# mapleSDuino-V0_1_011-eagle7.net
KiCad netlist of a schematic drawn in EAGLE
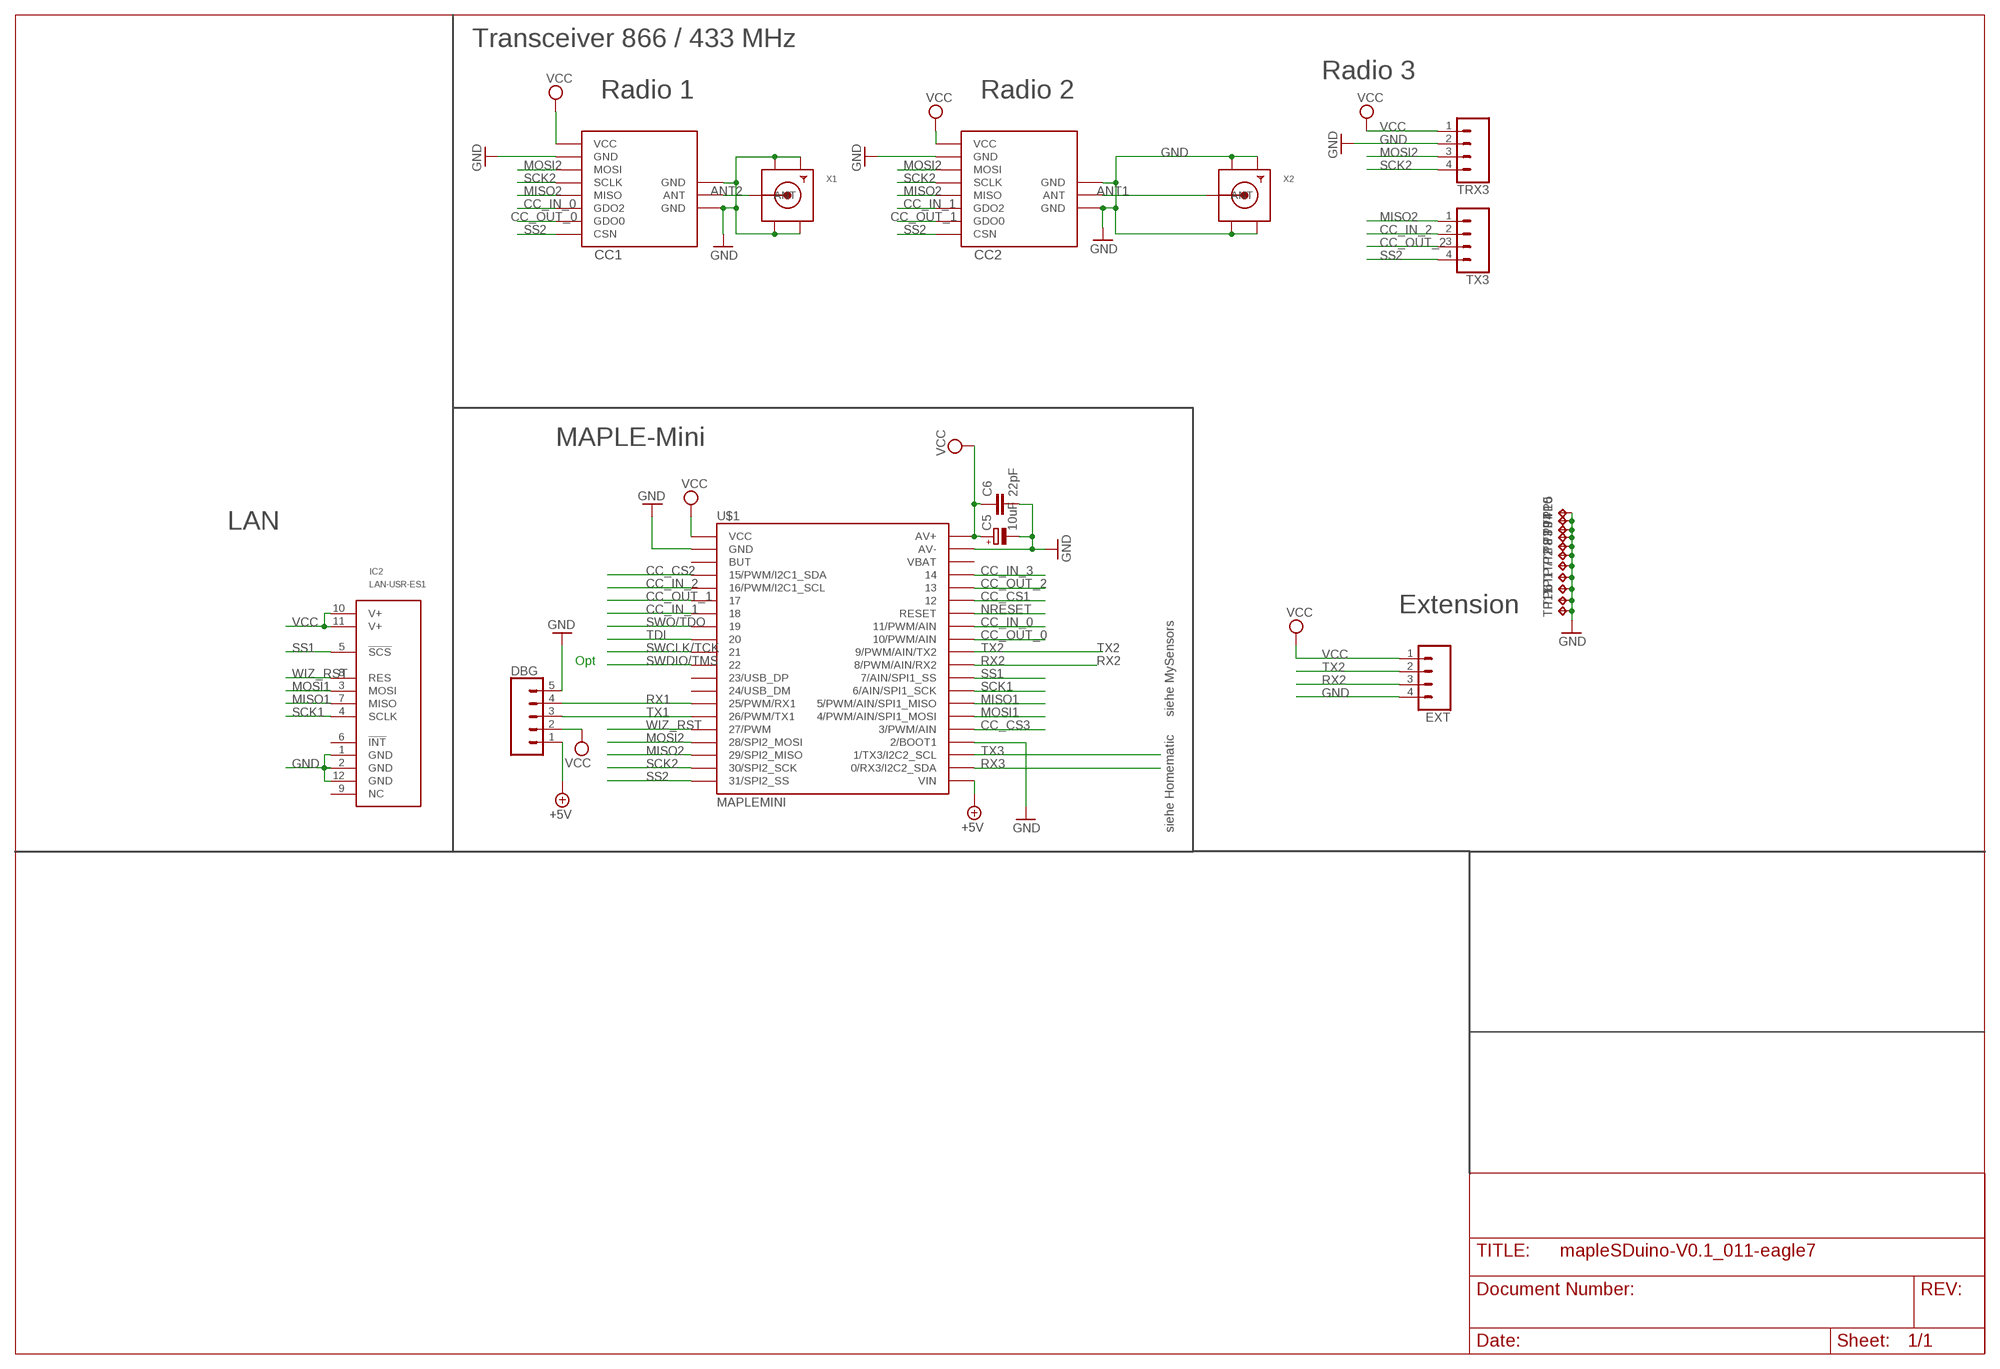
[diagram p0: schematic, sheet 1]

(export (version "E")
  (design (tool "Eeschema 10.0.6"))
  (components
    (comp (ref "C5")
      (value "10uF")
      (footprint "eagle-import:R_2012-12W")
      (libsource (lib "eagle-import") (part "CPOL-EUR/2012-12W"))
    )
    (comp (ref "C6")
      (value "22pF")
      (footprint "eagle-import:C0805")
      (libsource (lib "eagle-import") (part "C-EUC0805"))
    )
    (comp (ref "CC1")
      (value "CC1101")
      (footprint "eagle-import:CC1101_MODULE1_SMD")
      (libsource (lib "eagle-import") (part "CC1101_MODULE1SMD"))
    )
    (comp (ref "CC2")
      (value "CC1101_MODULE1SMD")
      (footprint "eagle-import:CC1101_MODULE1_SMD")
      (libsource (lib "eagle-import") (part "CC1101_MODULE1SMD"))
    )
    (comp (ref "DBG")
      (value "CONN_05LOCK")
      (footprint "eagle-import:1X05_LOCK")
      (libsource (lib "eagle-import") (part "CONN_05LOCK"))
    )
    (comp (ref "EXT")
      (value "CONN_04PTH")
      (footprint "eagle-import:1X04")
      (libsource (lib "eagle-import") (part "CONN_04PTH"))
    )
    (comp (ref "IC2")
      (value "LAN-USR-ES1")
      (footprint "eagle-import:USR-ES1")
      (libsource (lib "eagle-import") (part "LAN-USR-ES1"))
    )
    (comp (ref "TP1")
      (value "TPTP06SQ")
      (footprint "eagle-import:TP06SQ")
      (libsource (lib "eagle-import") (part "TPTP06SQ"))
    )
    (comp (ref "TP2")
      (value "TPTP06SQ")
      (footprint "eagle-import:TP06SQ")
      (libsource (lib "eagle-import") (part "TPTP06SQ"))
    )
    (comp (ref "TP3")
      (value "TPTP06SQ")
      (footprint "eagle-import:TP06SQ")
      (libsource (lib "eagle-import") (part "TPTP06SQ"))
    )
    (comp (ref "TP4")
      (value "TPTP06SQ")
      (footprint "eagle-import:TP06SQ")
      (libsource (lib "eagle-import") (part "TPTP06SQ"))
    )
    (comp (ref "TP5")
      (value "TPTP06SQ")
      (footprint "eagle-import:TP06SQ")
      (libsource (lib "eagle-import") (part "TPTP06SQ"))
    )
    (comp (ref "TP6")
      (value "TPTP06SQ")
      (footprint "eagle-import:TP06SQ")
      (libsource (lib "eagle-import") (part "TPTP06SQ"))
    )
    (comp (ref "TP7")
      (value "TPTP06SQ")
      (footprint "eagle-import:TP06SQ")
      (libsource (lib "eagle-import") (part "TPTP06SQ"))
    )
    (comp (ref "TP8")
      (value "TPTP06SQ")
      (footprint "eagle-import:TP06SQ")
      (libsource (lib "eagle-import") (part "TPTP06SQ"))
    )
    (comp (ref "TP9")
      (value "TPTP06SQ")
      (footprint "eagle-import:TP06SQ")
      (libsource (lib "eagle-import") (part "TPTP06SQ"))
    )
    (comp (ref "TP10")
      (value "TPTP06SQ")
      (footprint "eagle-import:TP06SQ")
      (libsource (lib "eagle-import") (part "TPTP06SQ"))
    )
    (comp (ref "TP11")
      (value "TPTP06SQ")
      (footprint "eagle-import:TP06SQ")
      (libsource (lib "eagle-import") (part "TPTP06SQ"))
    )
    (comp (ref "TRX3")
      (value "CONN_04PTH")
      (footprint "eagle-import:1X04")
      (libsource (lib "eagle-import") (part "CONN_04PTH"))
    )
    (comp (ref "TX3")
      (value "CONN_04PTH")
      (footprint "eagle-import:1X04")
      (libsource (lib "eagle-import") (part "CONN_04PTH"))
    )
    (comp (ref "U$1")
      (value "MAPLEMINI")
      (footprint "eagle-import:20-DIP")
      (libsource (lib "eagle-import") (part "MAPLEMINI"))
    )
    (comp (ref "X1")
      (value "SMACONNECTOR_EDGE")
      (footprint "eagle-import:SMA_EDGELAUNCH")
      (libsource (lib "eagle-import") (part "SMACONNECTOR_EDGE"))
    )
    (comp (ref "X2")
      (value "SMACONNECTOR_EDGE")
      (footprint "eagle-import:SMA_EDGELAUNCH")
      (libsource (lib "eagle-import") (part "SMACONNECTOR_EDGE"))
    )
  )
  (nets
    (net (code "1") (name "+5V") (class "Default")
      (node (ref "DBG") (pin "1") (pinfunction "1_1") (pintype "passive"))
      (node (ref "U$1") (pin "21") (pinfunction "VIN_21") (pintype "bidirectional"))
    )
    (net (code "2") (name "/ANT1") (class "Default")
      (node (ref "CC2") (pin "ANT") (pinfunction "ANT_ANT") (pintype "output"))
      (node (ref "X2") (pin "P") (pinfunction "ANT_P") (pintype "bidirectional"))
    )
    (net (code "3") (name "/ANT2") (class "Default")
      (node (ref "CC1") (pin "ANT") (pinfunction "ANT_ANT") (pintype "output"))
      (node (ref "X1") (pin "P") (pinfunction "ANT_P") (pintype "bidirectional"))
    )
    (net (code "4") (name "/CC_CS1") (class "Default")
      (node (ref "U$1") (pin "35") (pinfunction "12_35") (pintype "bidirectional"))
    )
    (net (code "5") (name "/CC_CS2") (class "Default")
      (node (ref "U$1") (pin "4") (pinfunction "15/PWM/I2C1_SDA_4") (pintype "bidirectional"))
    )
    (net (code "6") (name "/CC_CS3") (class "Default")
      (node (ref "U$1") (pin "25") (pinfunction "3/PWM/AIN_25") (pintype "bidirectional"))
    )
    (net (code "7") (name "/CC_IN_0") (class "Default")
      (node (ref "CC1") (pin "GDO2") (pinfunction "GDO2_GDO2") (pintype "bidirectional"))
      (node (ref "U$1") (pin "33") (pinfunction "11/PWM/AIN_33") (pintype "bidirectional"))
    )
    (net (code "8") (name "/CC_IN_1") (class "Default")
      (node (ref "CC2") (pin "GDO2") (pinfunction "GDO2_GDO2") (pintype "bidirectional"))
      (node (ref "U$1") (pin "7") (pinfunction "18_7") (pintype "bidirectional"))
    )
    (net (code "9") (name "/CC_IN_2") (class "Default")
      (node (ref "TX3") (pin "2") (pinfunction "2_2") (pintype "passive"))
      (node (ref "U$1") (pin "5") (pinfunction "16/PWM/I2C1_SCL_5") (pintype "bidirectional"))
    )
    (net (code "10") (name "/CC_IN_3") (class "Default")
      (node (ref "U$1") (pin "37") (pinfunction "14_37") (pintype "bidirectional"))
    )
    (net (code "11") (name "/CC_OUT_0") (class "Default")
      (node (ref "CC1") (pin "GDO0") (pinfunction "GDO0_GDO0") (pintype "bidirectional"))
      (node (ref "U$1") (pin "32") (pinfunction "10/PWM/AIN_32") (pintype "bidirectional"))
    )
    (net (code "12") (name "/CC_OUT_1") (class "Default")
      (node (ref "CC2") (pin "GDO0") (pinfunction "GDO0_GDO0") (pintype "bidirectional"))
      (node (ref "U$1") (pin "6") (pinfunction "17_6") (pintype "bidirectional"))
    )
    (net (code "13") (name "/CC_OUT_2") (class "Default")
      (node (ref "TX3") (pin "3") (pinfunction "3_3") (pintype "passive"))
      (node (ref "U$1") (pin "36") (pinfunction "13_36") (pintype "bidirectional"))
    )
    (net (code "14") (name "/MISO1") (class "Default")
      (node (ref "IC2") (pin "7") (pinfunction "MISO_7") (pintype "bidirectional"))
      (node (ref "U$1") (pin "27") (pinfunction "5/PWM/AIN/SPI1_MISO_27") (pintype "bidirectional"))
    )
    (net (code "15") (name "/MISO2") (class "Default")
      (node (ref "CC1") (pin "MISO") (pinfunction "MISO_MISO") (pintype "bidirectional"))
      (node (ref "CC2") (pin "MISO") (pinfunction "MISO_MISO") (pintype "bidirectional"))
      (node (ref "TX3") (pin "1") (pinfunction "1_1") (pintype "passive"))
      (node (ref "U$1") (pin "18") (pinfunction "29/SPI2_MISO_18") (pintype "bidirectional"))
    )
    (net (code "16") (name "/MOSI1") (class "Default")
      (node (ref "IC2") (pin "3") (pinfunction "MOSI_3") (pintype "bidirectional"))
      (node (ref "U$1") (pin "26") (pinfunction "4/PWM/AIN/SPI1_MOSI_26") (pintype "bidirectional"))
    )
    (net (code "17") (name "/MOSI2") (class "Default")
      (node (ref "CC1") (pin "MOSI") (pinfunction "MOSI_MOSI") (pintype "bidirectional"))
      (node (ref "CC2") (pin "MOSI") (pinfunction "MOSI_MOSI") (pintype "bidirectional"))
      (node (ref "TRX3") (pin "3") (pinfunction "3_3") (pintype "passive"))
      (node (ref "U$1") (pin "17") (pinfunction "28/SPI2_MOSI_17") (pintype "bidirectional"))
    )
    (net (code "18") (name "/NRESET") (class "Default")
      (node (ref "U$1") (pin "34") (pinfunction "RESET_34") (pintype "bidirectional"))
    )
    (net (code "19") (name "/RX1") (class "Default")
      (node (ref "DBG") (pin "4") (pinfunction "4_4") (pintype "passive"))
      (node (ref "U$1") (pin "14") (pinfunction "25/PWM/RX1_14") (pintype "bidirectional"))
    )
    (net (code "20") (name "/RX2") (class "Default")
      (node (ref "EXT") (pin "3") (pinfunction "3_3") (pintype "passive"))
      (node (ref "U$1") (pin "30") (pinfunction "8/PWM/AIN/RX2_30") (pintype "bidirectional"))
    )
    (net (code "21") (name "/RX3") (class "Default")
      (node (ref "U$1") (pin "22") (pinfunction "0/RX3/I2C2_SDA_22") (pintype "bidirectional"))
    )
    (net (code "22") (name "/SCK1") (class "Default")
      (node (ref "IC2") (pin "4") (pinfunction "SCLK_4") (pintype "input"))
      (node (ref "U$1") (pin "28") (pinfunction "6/AIN/SPI1_SCK_28") (pintype "bidirectional"))
    )
    (net (code "23") (name "/SCK2") (class "Default")
      (node (ref "CC1") (pin "SCLK") (pinfunction "SCLK_SCLK") (pintype "bidirectional"))
      (node (ref "CC2") (pin "SCLK") (pinfunction "SCLK_SCLK") (pintype "bidirectional"))
      (node (ref "TRX3") (pin "4") (pinfunction "4_4") (pintype "passive"))
      (node (ref "U$1") (pin "19") (pinfunction "30/SPI2_SCK_19") (pintype "bidirectional"))
    )
    (net (code "24") (name "/SS1") (class "Default")
      (node (ref "IC2") (pin "5") (pinfunction "~{SCS}_5") (pintype "input"))
      (node (ref "U$1") (pin "29") (pinfunction "7/AIN/SPI1_SS_29") (pintype "bidirectional"))
    )
    (net (code "25") (name "/SS2") (class "Default")
      (node (ref "CC1") (pin "CSN") (pinfunction "CSN_CSN") (pintype "bidirectional"))
      (node (ref "CC2") (pin "CSN") (pinfunction "CSN_CSN") (pintype "bidirectional"))
      (node (ref "TX3") (pin "4") (pinfunction "4_4") (pintype "passive"))
      (node (ref "U$1") (pin "20") (pinfunction "31/SPI2_SS_20") (pintype "bidirectional"))
    )
    (net (code "26") (name "/SWCLK{slash}TCK") (class "Default")
      (node (ref "U$1") (pin "10") (pinfunction "21_10") (pintype "bidirectional"))
    )
    (net (code "27") (name "/SWDIO{slash}TMS") (class "Default")
      (node (ref "U$1") (pin "11") (pinfunction "22_11") (pintype "bidirectional"))
    )
    (net (code "28") (name "/SWO{slash}TDO") (class "Default")
      (node (ref "U$1") (pin "8") (pinfunction "19_8") (pintype "bidirectional"))
    )
    (net (code "29") (name "/TDI") (class "Default")
      (node (ref "U$1") (pin "9") (pinfunction "20_9") (pintype "bidirectional"))
    )
    (net (code "30") (name "/TX1") (class "Default")
      (node (ref "DBG") (pin "3") (pinfunction "3_3") (pintype "passive"))
      (node (ref "U$1") (pin "15") (pinfunction "26/PWM/TX1_15") (pintype "bidirectional"))
    )
    (net (code "31") (name "/TX2") (class "Default")
      (node (ref "EXT") (pin "2") (pinfunction "2_2") (pintype "passive"))
      (node (ref "U$1") (pin "31") (pinfunction "9/PWM/AIN/TX2_31") (pintype "bidirectional"))
    )
    (net (code "32") (name "/TX3") (class "Default")
      (node (ref "U$1") (pin "23") (pinfunction "1/TX3/I2C2_SCL_23") (pintype "bidirectional"))
    )
    (net (code "33") (name "/WIZ_RST") (class "Default")
      (node (ref "IC2") (pin "8") (pinfunction "RES_8") (pintype "input"))
      (node (ref "U$1") (pin "16") (pinfunction "27/PWM_16") (pintype "bidirectional"))
    )
    (net (code "34") (name "GND") (class "Default")
      (node (ref "C5") (pin "-") (pinfunction "-_-") (pintype "passive"))
      (node (ref "C6") (pin "2") (pinfunction "2_2") (pintype "passive"))
      (node (ref "CC1") (pin "GND@0") (pinfunction "GND_GND@0") (pintype "power_in"))
      (node (ref "CC1") (pin "GND@1") (pinfunction "GND_GND@1") (pintype "power_in"))
      (node (ref "CC1") (pin "GND@2") (pinfunction "GND_GND@2") (pintype "power_in"))
      (node (ref "CC2") (pin "GND@0") (pinfunction "GND_GND@0") (pintype "power_in"))
      (node (ref "CC2") (pin "GND@1") (pinfunction "GND_GND@1") (pintype "power_in"))
      (node (ref "CC2") (pin "GND@2") (pinfunction "GND_GND@2") (pintype "power_in"))
      (node (ref "DBG") (pin "5") (pinfunction "5_5") (pintype "passive"))
      (node (ref "EXT") (pin "4") (pinfunction "4_4") (pintype "passive"))
      (node (ref "IC2") (pin "1") (pinfunction "GND_1") (pintype "power_in"))
      (node (ref "IC2") (pin "12") (pinfunction "GND_12") (pintype "power_in"))
      (node (ref "IC2") (pin "2") (pinfunction "GND_2") (pintype "power_in"))
      (node (ref "TP1") (pin "TP") (pinfunction "TP_TP") (pintype "input"))
      (node (ref "TP10") (pin "TP") (pinfunction "TP_TP") (pintype "input"))
      (node (ref "TP11") (pin "TP") (pinfunction "TP_TP") (pintype "input"))
      (node (ref "TP2") (pin "TP") (pinfunction "TP_TP") (pintype "input"))
      (node (ref "TP3") (pin "TP") (pinfunction "TP_TP") (pintype "input"))
      (node (ref "TP4") (pin "TP") (pinfunction "TP_TP") (pintype "input"))
      (node (ref "TP5") (pin "TP") (pinfunction "TP_TP") (pintype "input"))
      (node (ref "TP6") (pin "TP") (pinfunction "TP_TP") (pintype "input"))
      (node (ref "TP7") (pin "TP") (pinfunction "TP_TP") (pintype "input"))
      (node (ref "TP8") (pin "TP") (pinfunction "TP_TP") (pintype "input"))
      (node (ref "TP9") (pin "TP") (pinfunction "TP_TP") (pintype "input"))
      (node (ref "TRX3") (pin "2") (pinfunction "2_2") (pintype "passive"))
      (node (ref "U$1") (pin "2") (pinfunction "GND_2") (pintype "bidirectional"))
      (node (ref "U$1") (pin "24") (pinfunction "2/BOOT1_24") (pintype "bidirectional"))
      (node (ref "U$1") (pin "39") (pinfunction "AV-_39") (pintype "bidirectional"))
      (node (ref "X1") (pin "GND@1") (pinfunction "GND4_GND@1") (pintype "power_in"))
      (node (ref "X1") (pin "GND@2") (pinfunction "GND3_GND@2") (pintype "power_in"))
      (node (ref "X1") (pin "GND@3") (pinfunction "GND2_GND@3") (pintype "power_in"))
      (node (ref "X1") (pin "GND@4") (pinfunction "GND1_GND@4") (pintype "power_in"))
      (node (ref "X2") (pin "GND@1") (pinfunction "GND4_GND@1") (pintype "power_in"))
      (node (ref "X2") (pin "GND@2") (pinfunction "GND3_GND@2") (pintype "power_in"))
      (node (ref "X2") (pin "GND@3") (pinfunction "GND2_GND@3") (pintype "power_in"))
      (node (ref "X2") (pin "GND@4") (pinfunction "GND1_GND@4") (pintype "power_in"))
    )
    (net (code "35") (name "VCC") (class "Default")
      (node (ref "C5") (pin "+") (pinfunction "+_+") (pintype "passive"))
      (node (ref "C6") (pin "1") (pinfunction "1_1") (pintype "passive"))
      (node (ref "CC1") (pin "VCC") (pinfunction "VCC_VCC") (pintype "power_in"))
      (node (ref "CC2") (pin "VCC") (pinfunction "VCC_VCC") (pintype "power_in"))
      (node (ref "DBG") (pin "2") (pinfunction "2_2") (pintype "passive"))
      (node (ref "EXT") (pin "1") (pinfunction "1_1") (pintype "passive"))
      (node (ref "IC2") (pin "10") (pinfunction "V+_10") (pintype "power_in"))
      (node (ref "IC2") (pin "11") (pinfunction "V+_11") (pintype "power_in"))
      (node (ref "TRX3") (pin "1") (pinfunction "1_1") (pintype "passive"))
      (node (ref "U$1") (pin "1") (pinfunction "VCC_1") (pintype "bidirectional"))
      (node (ref "U$1") (pin "40") (pinfunction "AV+_40") (pintype "bidirectional"))
    )
    (net (code "36") (name "unconnected-(IC2-NC-Pad9)") (class "Default")
      (node (ref "IC2") (pin "9") (pinfunction "NC_9") (pintype "no_connect"))
    )
    (net (code "37") (name "unconnected-(IC2-~{INT}-Pad6)") (class "Default")
      (node (ref "IC2") (pin "6") (pinfunction "~{INT}_6") (pintype "output"))
    )
    (net (code "38") (name "unconnected-(U$1-23{slash}USB_DP-Pad12)") (class "Default")
      (node (ref "U$1") (pin "12") (pinfunction "23/USB_DP_12") (pintype "bidirectional"))
    )
    (net (code "39") (name "unconnected-(U$1-24{slash}USB_DM-Pad13)") (class "Default")
      (node (ref "U$1") (pin "13") (pinfunction "24/USB_DM_13") (pintype "bidirectional"))
    )
    (net (code "40") (name "unconnected-(U$1-BUT-Pad3)") (class "Default")
      (node (ref "U$1") (pin "3") (pinfunction "BUT_3") (pintype "bidirectional"))
    )
    (net (code "41") (name "unconnected-(U$1-VBAT-Pad38)") (class "Default")
      (node (ref "U$1") (pin "38") (pinfunction "VBAT_38") (pintype "bidirectional"))
    )
  )
)
